# H4ptiX.net
KiCad netlist of a schematic drawn in EasyEDA Pro
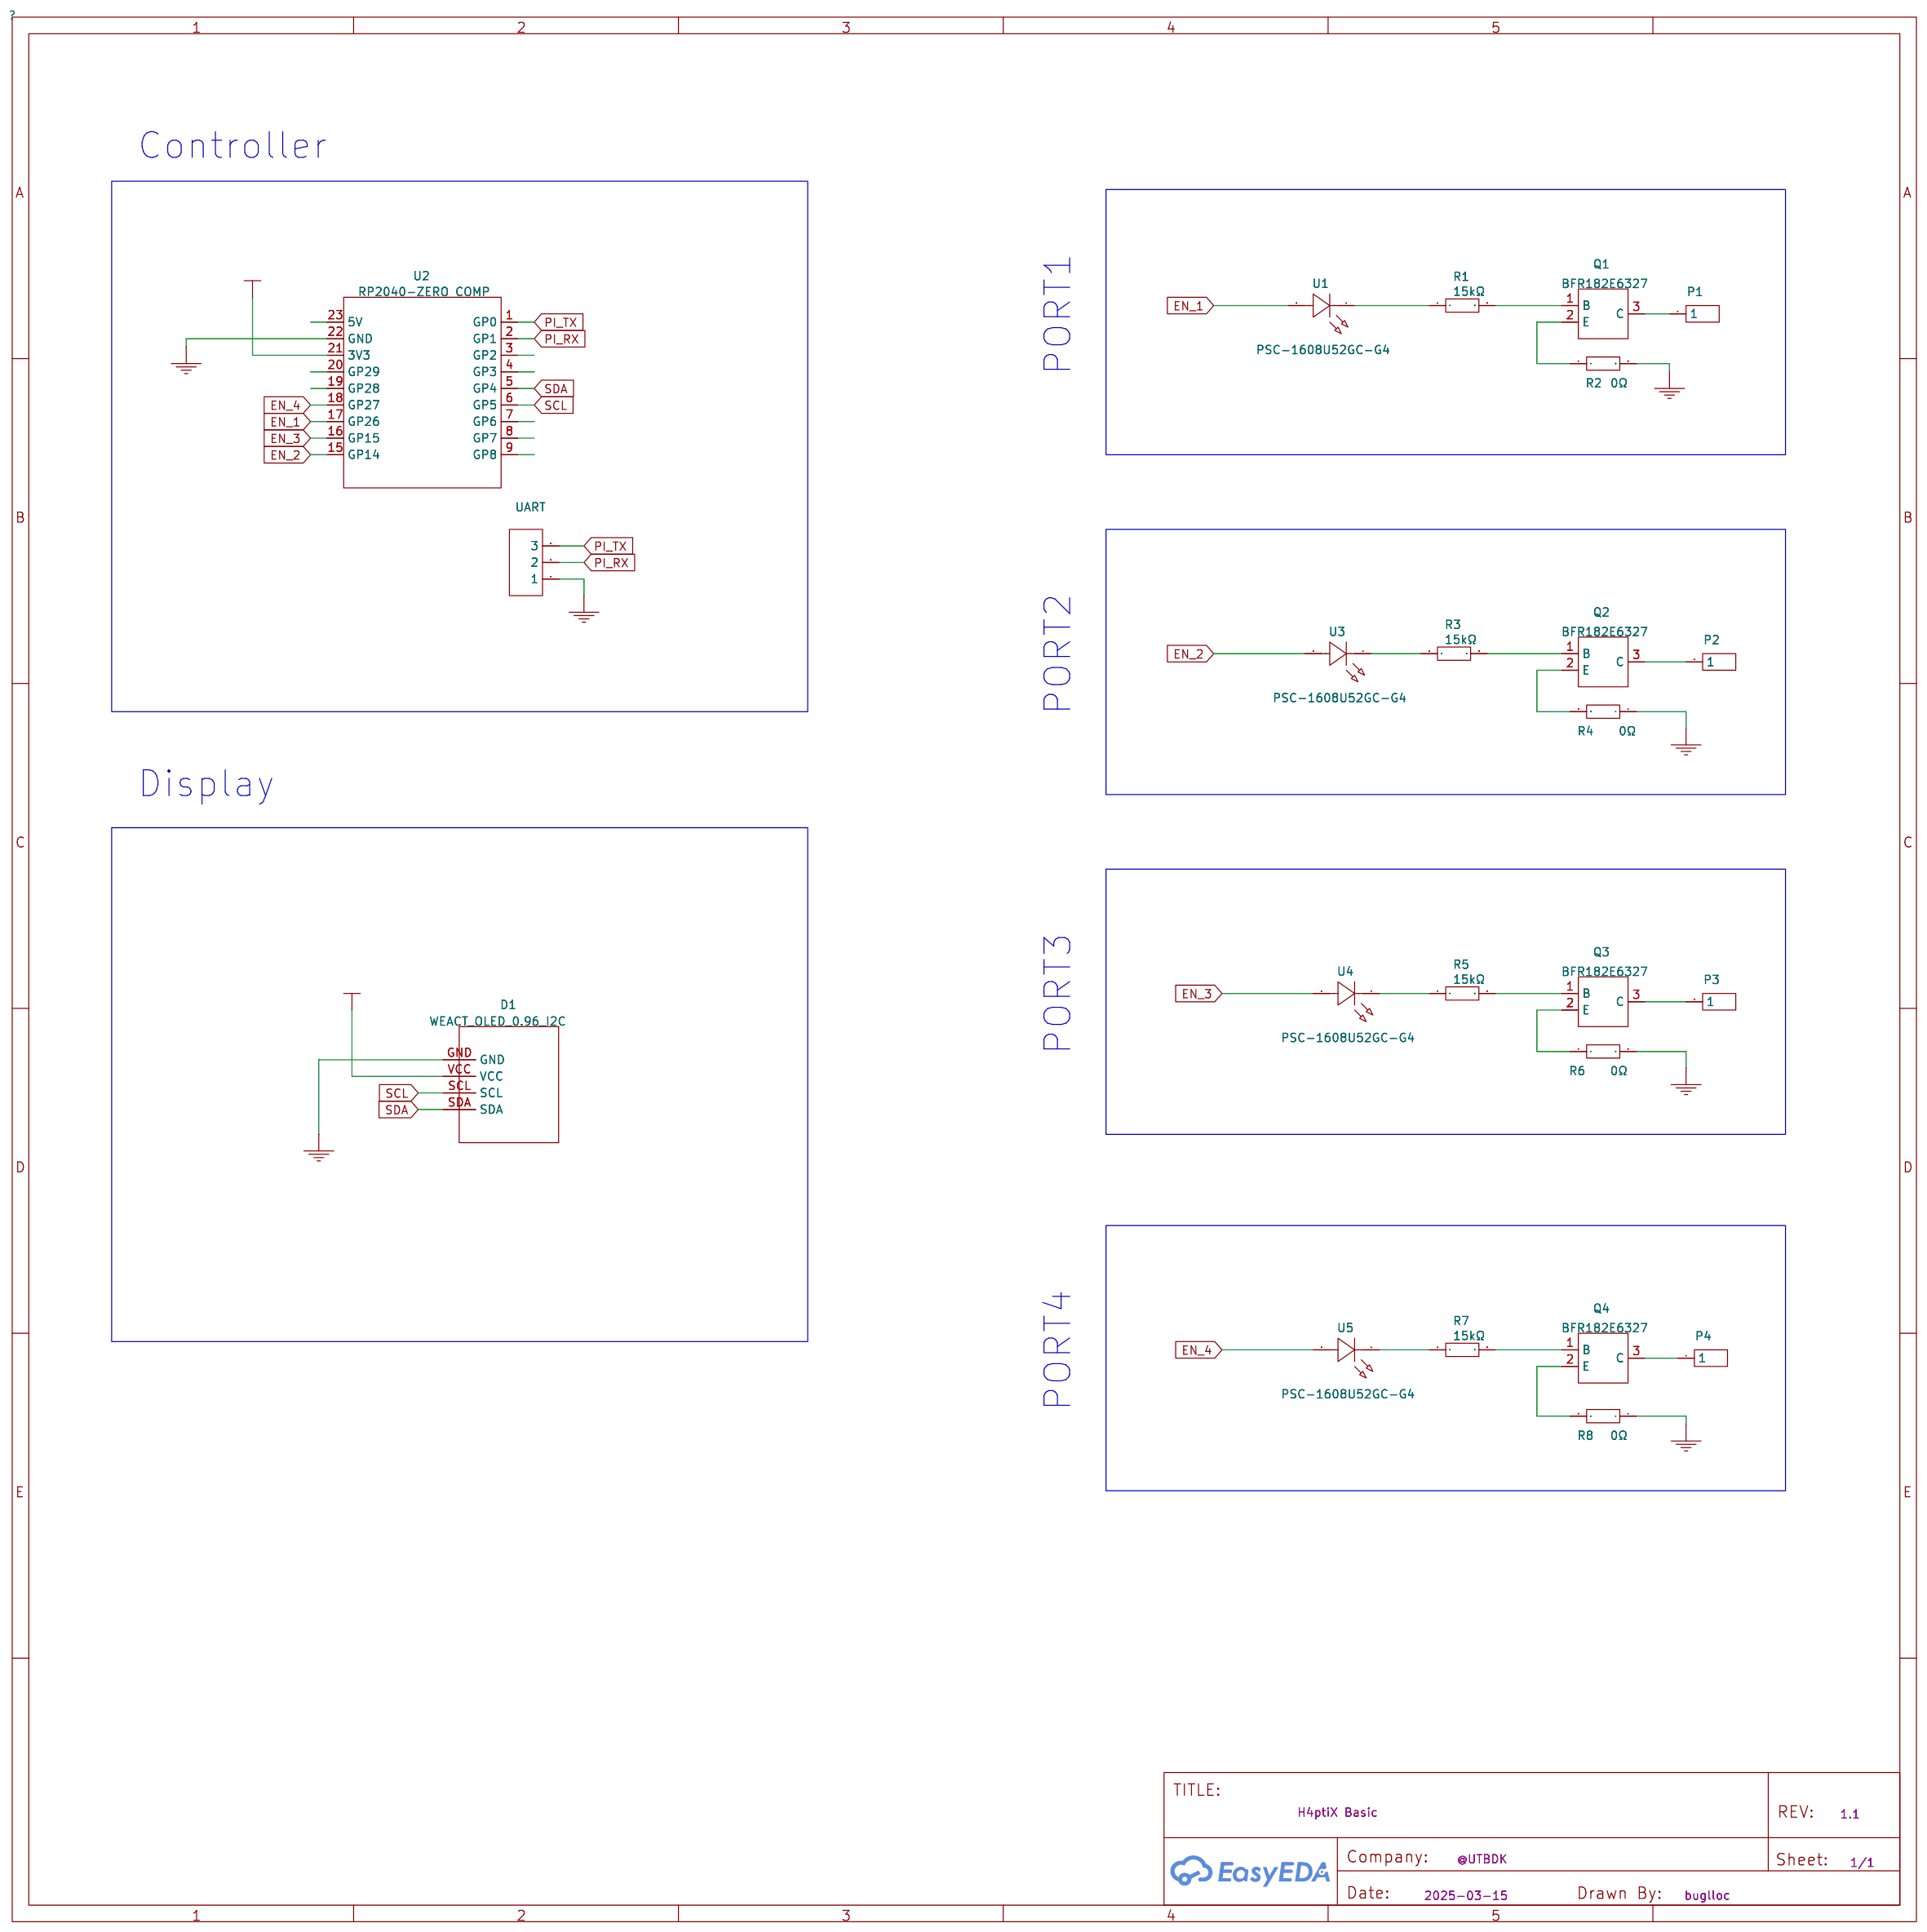
[diagram p0: schematic sheet]

(export (version "E")
  (design (tool "Eeschema 10.0.6"))
  (components
    (comp (ref "D1")
      (value "WEACT_OLED_0.96_I2C")
      (footprint "easyedapro:WEACT_OLED_0.96_I2C")
      (fields (field (name "Contributor") "buglloc"))
      (libsource (lib "easyedapro") (part "WEACT_OLED_0.96_I2C"))
    )
    (comp (ref "P1")
      (value "HDR-M-2.54_1x1")
      (footprint "easyedapro:HDR-M-2.54_1X1")
      (fields (field (name "Contributor") "LCEDA_Lib"))
      (libsource (lib "easyedapro") (part "HDR-M-2.54_1x1"))
    )
    (comp (ref "P2")
      (value "HDR-M-2.54_1x1")
      (footprint "easyedapro:HDR-M-2.54_1X1")
      (fields (field (name "Contributor") "LCEDA_Lib"))
      (libsource (lib "easyedapro") (part "HDR-M-2.54_1x1"))
    )
    (comp (ref "P3")
      (value "HDR-M-2.54_1x1")
      (footprint "easyedapro:HDR-M-2.54_1X1")
      (fields (field (name "Contributor") "LCEDA_Lib"))
      (libsource (lib "easyedapro") (part "HDR-M-2.54_1x1"))
    )
    (comp (ref "P4")
      (value "HDR-M-2.54_1x1")
      (footprint "easyedapro:HDR-M-2.54_1X1")
      (fields (field (name "Contributor") "LCEDA_Lib"))
      (libsource (lib "easyedapro") (part "HDR-M-2.54_1x1"))
    )
    (comp (ref "Q1")
      (value "BFR182E6327")
      (footprint "easyedapro:SOT-23-3_L2.9-W1.3-P1.90-LS2.4-BR")
      (fields (field (name "Manufacturer") "Infineon(英飞凌)") (field (name "Contributor") "LCSC"))
      (libsource (lib "easyedapro") (part "BFR182E6327"))
    )
    (comp (ref "Q2")
      (value "BFR182E6327")
      (footprint "easyedapro:SOT-23-3_L2.9-W1.3-P1.90-LS2.4-BR")
      (fields (field (name "Manufacturer") "Infineon(英飞凌)") (field (name "Contributor") "LCSC"))
      (libsource (lib "easyedapro") (part "BFR182E6327"))
    )
    (comp (ref "Q3")
      (value "BFR182E6327")
      (footprint "easyedapro:SOT-23-3_L2.9-W1.3-P1.90-LS2.4-BR")
      (fields (field (name "Manufacturer") "Infineon(英飞凌)") (field (name "Contributor") "LCSC"))
      (libsource (lib "easyedapro") (part "BFR182E6327"))
    )
    (comp (ref "Q4")
      (value "BFR182E6327")
      (footprint "easyedapro:SOT-23-3_L2.9-W1.3-P1.90-LS2.4-BR")
      (fields (field (name "Manufacturer") "Infineon(英飞凌)") (field (name "Contributor") "LCSC"))
      (libsource (lib "easyedapro") (part "BFR182E6327"))
    )
    (comp (ref "R1")
      (value "15kΩ")
      (footprint "easyedapro:R0603")
      (fields
        (field (name "Manufacturer Part") "0603WAF1502T5E")
        (field (name "Manufacturer") "UNI-ROYAL(厚声)")
      )
      (libsource (lib "easyedapro") (part "15kΩ"))
    )
    (comp (ref "R2")
      (value "0Ω")
      (footprint "easyedapro:R0603")
      (fields
        (field (name "Manufacturer Part") "0603WAF0000T5E")
        (field (name "Manufacturer") "UNI-ROYAL(厚声)")
      )
      (libsource (lib "easyedapro") (part "0Ω"))
    )
    (comp (ref "R3")
      (value "15kΩ")
      (footprint "easyedapro:R0603")
      (fields
        (field (name "Manufacturer Part") "0603WAF1502T5E")
        (field (name "Manufacturer") "UNI-ROYAL(厚声)")
      )
      (libsource (lib "easyedapro") (part "15kΩ"))
    )
    (comp (ref "R4")
      (value "0Ω")
      (footprint "easyedapro:R0603")
      (fields
        (field (name "Manufacturer Part") "0603WAF0000T5E")
        (field (name "Manufacturer") "UNI-ROYAL(厚声)")
      )
      (libsource (lib "") (part "0Ω_1"))
    )
    (comp (ref "R5")
      (value "15kΩ")
      (footprint "easyedapro:R0603")
      (fields
        (field (name "Manufacturer Part") "0603WAF1502T5E")
        (field (name "Manufacturer") "UNI-ROYAL(厚声)")
      )
      (libsource (lib "easyedapro") (part "15kΩ"))
    )
    (comp (ref "R6")
      (value "0Ω")
      (footprint "easyedapro:R0603")
      (fields
        (field (name "Manufacturer Part") "0603WAF0000T5E")
        (field (name "Manufacturer") "UNI-ROYAL(厚声)")
      )
      (libsource (lib "easyedapro") (part "0Ω"))
    )
    (comp (ref "R7")
      (value "15kΩ")
      (footprint "easyedapro:R0603")
      (fields
        (field (name "Manufacturer Part") "0603WAF1502T5E")
        (field (name "Manufacturer") "UNI-ROYAL(厚声)")
      )
      (libsource (lib "easyedapro") (part "15kΩ"))
    )
    (comp (ref "R8")
      (value "0Ω")
      (footprint "easyedapro:R0603")
      (fields
        (field (name "Manufacturer Part") "0603WAF0000T5E")
        (field (name "Manufacturer") "UNI-ROYAL(厚声)")
      )
      (libsource (lib "") (part "0Ω_1"))
    )
    (comp (ref "U1")
      (value "PSC-1608U52GC-G4")
      (footprint "easyedapro:LED0603-RD_GREEN")
      (fields (field (name "Manufacturer") "HONGLITRONIC(鸿利光电)") (field (name "Contributor") "lcsc"))
      (libsource (lib "easyedapro") (part "PSC-1608U52GC-G4"))
    )
    (comp (ref "U2")
      (value "RP2040-ZERO COMP")
      (footprint "easyedapro:RP2040-ZERO NO FOOTS")
      (fields (field (name "Contributor") "buglloc"))
      (libsource (lib "easyedapro") (part "RP2040-ZERO COMP"))
    )
    (comp (ref "U3")
      (value "PSC-1608U52GC-G4")
      (footprint "easyedapro:LED0603-RD_GREEN")
      (fields (field (name "Manufacturer") "HONGLITRONIC(鸿利光电)") (field (name "Contributor") "lcsc"))
      (libsource (lib "easyedapro") (part "PSC-1608U52GC-G4"))
    )
    (comp (ref "U4")
      (value "PSC-1608U52GC-G4")
      (footprint "easyedapro:LED0603-RD_GREEN")
      (fields (field (name "Manufacturer") "HONGLITRONIC(鸿利光电)") (field (name "Contributor") "lcsc"))
      (libsource (lib "easyedapro") (part "PSC-1608U52GC-G4"))
    )
    (comp (ref "U5")
      (value "PSC-1608U52GC-G4")
      (footprint "easyedapro:LED0603-RD_GREEN")
      (fields (field (name "Manufacturer") "HONGLITRONIC(鸿利光电)") (field (name "Contributor") "lcsc"))
      (libsource (lib "easyedapro") (part "PSC-1608U52GC-G4"))
    )
    (comp (ref "UART")
      (value "UART")
      (footprint "easyedapro:HDR-M-2.54_1X3")
      (fields (field (name "Contributor") "LCEDA_Lib"))
      (libsource (lib "easyedapro") (part "UART"))
    )
  )
  (nets
    (net (code "1") (name "3V3") (class "Default")
      (node (ref "D1") (pin "VCC") (pinfunction "VCC_VCC") (pintype "bidirectional"))
      (node (ref "U2") (pin "21") (pinfunction "3V3_21") (pintype "unspecified"))
    )
    (net (code "2") (name "EN_1") (class "Default")
      (node (ref "U1") (pin "2") (pinfunction "A_2") (pintype "unspecified"))
      (node (ref "U2") (pin "17") (pinfunction "GP26_17") (pintype "unspecified"))
    )
    (net (code "3") (name "EN_2") (class "Default")
      (node (ref "U2") (pin "15") (pinfunction "GP14_15") (pintype "unspecified"))
      (node (ref "U3") (pin "2") (pinfunction "A_2") (pintype "unspecified"))
    )
    (net (code "4") (name "EN_3") (class "Default")
      (node (ref "U2") (pin "16") (pinfunction "GP15_16") (pintype "unspecified"))
      (node (ref "U4") (pin "2") (pinfunction "A_2") (pintype "unspecified"))
    )
    (net (code "5") (name "EN_4") (class "Default")
      (node (ref "U2") (pin "18") (pinfunction "GP27_18") (pintype "unspecified"))
      (node (ref "U5") (pin "2") (pinfunction "A_2") (pintype "unspecified"))
    )
    (net (code "6") (name "GND") (class "Default")
      (node (ref "D1") (pin "GND") (pinfunction "GND_GND") (pintype "bidirectional"))
      (node (ref "R2") (pin "2") (pinfunction "2_2") (pintype "input"))
      (node (ref "R4") (pin "1") (pinfunction "1_1") (pintype "input"))
      (node (ref "R6") (pin "2") (pinfunction "2_2") (pintype "input"))
      (node (ref "R8") (pin "1") (pinfunction "1_1") (pintype "input"))
      (node (ref "U2") (pin "22") (pinfunction "GND_22") (pintype "unspecified"))
      (node (ref "UART") (pin "1") (pinfunction "1_1") (pintype "input"))
    )
    (net (code "7") (name "Net-(Q1-B)") (class "Default")
      (node (ref "Q1") (pin "1") (pinfunction "B_1") (pintype "unspecified"))
      (node (ref "R1") (pin "2") (pinfunction "2_2") (pintype "input"))
    )
    (net (code "8") (name "Net-(Q1-C)") (class "Default")
      (node (ref "P1") (pin "1") (pinfunction "1_1") (pintype "input"))
      (node (ref "Q1") (pin "3") (pinfunction "C_3") (pintype "unspecified"))
    )
    (net (code "9") (name "Net-(Q1-E)") (class "Default")
      (node (ref "Q1") (pin "2") (pinfunction "E_2") (pintype "unspecified"))
      (node (ref "R2") (pin "1") (pinfunction "1_1") (pintype "input"))
    )
    (net (code "10") (name "Net-(Q2-B)") (class "Default")
      (node (ref "Q2") (pin "1") (pinfunction "B_1") (pintype "unspecified"))
      (node (ref "R3") (pin "2") (pinfunction "2_2") (pintype "input"))
    )
    (net (code "11") (name "Net-(Q2-C)") (class "Default")
      (node (ref "P2") (pin "1") (pinfunction "1_1") (pintype "input"))
      (node (ref "Q2") (pin "3") (pinfunction "C_3") (pintype "unspecified"))
    )
    (net (code "12") (name "Net-(Q2-E)") (class "Default")
      (node (ref "Q2") (pin "2") (pinfunction "E_2") (pintype "unspecified"))
      (node (ref "R4") (pin "2") (pinfunction "2_2") (pintype "input"))
    )
    (net (code "13") (name "Net-(Q3-B)") (class "Default")
      (node (ref "Q3") (pin "1") (pinfunction "B_1") (pintype "unspecified"))
      (node (ref "R5") (pin "2") (pinfunction "2_2") (pintype "input"))
    )
    (net (code "14") (name "Net-(Q3-C)") (class "Default")
      (node (ref "P3") (pin "1") (pinfunction "1_1") (pintype "input"))
      (node (ref "Q3") (pin "3") (pinfunction "C_3") (pintype "unspecified"))
    )
    (net (code "15") (name "Net-(Q3-E)") (class "Default")
      (node (ref "Q3") (pin "2") (pinfunction "E_2") (pintype "unspecified"))
      (node (ref "R6") (pin "1") (pinfunction "1_1") (pintype "input"))
    )
    (net (code "16") (name "Net-(Q4-B)") (class "Default")
      (node (ref "Q4") (pin "1") (pinfunction "B_1") (pintype "unspecified"))
      (node (ref "R7") (pin "2") (pinfunction "2_2") (pintype "input"))
    )
    (net (code "17") (name "Net-(Q4-C)") (class "Default")
      (node (ref "P4") (pin "1") (pinfunction "1_1") (pintype "input"))
      (node (ref "Q4") (pin "3") (pinfunction "C_3") (pintype "unspecified"))
    )
    (net (code "18") (name "Net-(Q4-E)") (class "Default")
      (node (ref "Q4") (pin "2") (pinfunction "E_2") (pintype "unspecified"))
      (node (ref "R8") (pin "2") (pinfunction "2_2") (pintype "input"))
    )
    (net (code "19") (name "Net-(U1-K)") (class "Default")
      (node (ref "R1") (pin "1") (pinfunction "1_1") (pintype "input"))
      (node (ref "U1") (pin "1") (pinfunction "K_1") (pintype "unspecified"))
    )
    (net (code "20") (name "Net-(U3-K)") (class "Default")
      (node (ref "R3") (pin "1") (pinfunction "1_1") (pintype "input"))
      (node (ref "U3") (pin "1") (pinfunction "K_1") (pintype "unspecified"))
    )
    (net (code "21") (name "Net-(U4-K)") (class "Default")
      (node (ref "R5") (pin "1") (pinfunction "1_1") (pintype "input"))
      (node (ref "U4") (pin "1") (pinfunction "K_1") (pintype "unspecified"))
    )
    (net (code "22") (name "Net-(U5-K)") (class "Default")
      (node (ref "R7") (pin "1") (pinfunction "1_1") (pintype "input"))
      (node (ref "U5") (pin "1") (pinfunction "K_1") (pintype "unspecified"))
    )
    (net (code "23") (name "PI_RX") (class "Default")
      (node (ref "U2") (pin "2") (pinfunction "GP1_2") (pintype "unspecified"))
      (node (ref "UART") (pin "2") (pinfunction "2_2") (pintype "input"))
    )
    (net (code "24") (name "PI_TX") (class "Default")
      (node (ref "U2") (pin "1") (pinfunction "GP0_1") (pintype "unspecified"))
      (node (ref "UART") (pin "3") (pinfunction "3_3") (pintype "input"))
    )
    (net (code "25") (name "SCL") (class "Default")
      (node (ref "D1") (pin "SCL") (pinfunction "SCL_SCL") (pintype "bidirectional"))
      (node (ref "U2") (pin "6") (pinfunction "GP5_6") (pintype "unspecified"))
    )
    (net (code "26") (name "SDA") (class "Default")
      (node (ref "D1") (pin "SDA") (pinfunction "SDA_SDA") (pintype "bidirectional"))
      (node (ref "U2") (pin "5") (pinfunction "GP4_5") (pintype "unspecified"))
    )
    (net (code "27") (name "unconnected-(U2-5V-Pad23)") (class "Default")
      (node (ref "U2") (pin "23") (pinfunction "5V_23") (pintype "unspecified"))
    )
    (net (code "28") (name "unconnected-(U2-GP2-Pad3)") (class "Default")
      (node (ref "U2") (pin "3") (pinfunction "GP2_3") (pintype "unspecified"))
    )
    (net (code "29") (name "unconnected-(U2-GP3-Pad4)") (class "Default")
      (node (ref "U2") (pin "4") (pinfunction "GP3_4") (pintype "unspecified"))
    )
    (net (code "30") (name "unconnected-(U2-GP6-Pad7)") (class "Default")
      (node (ref "U2") (pin "7") (pinfunction "GP6_7") (pintype "unspecified"))
    )
    (net (code "31") (name "unconnected-(U2-GP7-Pad8)") (class "Default")
      (node (ref "U2") (pin "8") (pinfunction "GP7_8") (pintype "unspecified"))
    )
    (net (code "32") (name "unconnected-(U2-GP8-Pad9)") (class "Default")
      (node (ref "U2") (pin "9") (pinfunction "GP8_9") (pintype "unspecified"))
    )
    (net (code "33") (name "unconnected-(U2-GP28-Pad19)") (class "Default")
      (node (ref "U2") (pin "19") (pinfunction "GP28_19") (pintype "unspecified"))
    )
    (net (code "34") (name "unconnected-(U2-GP29-Pad20)") (class "Default")
      (node (ref "U2") (pin "20") (pinfunction "GP29_20") (pintype "unspecified"))
    )
  )
)
